# Sheet1.net
KiCad netlist of a schematic drawn in Altium Designer
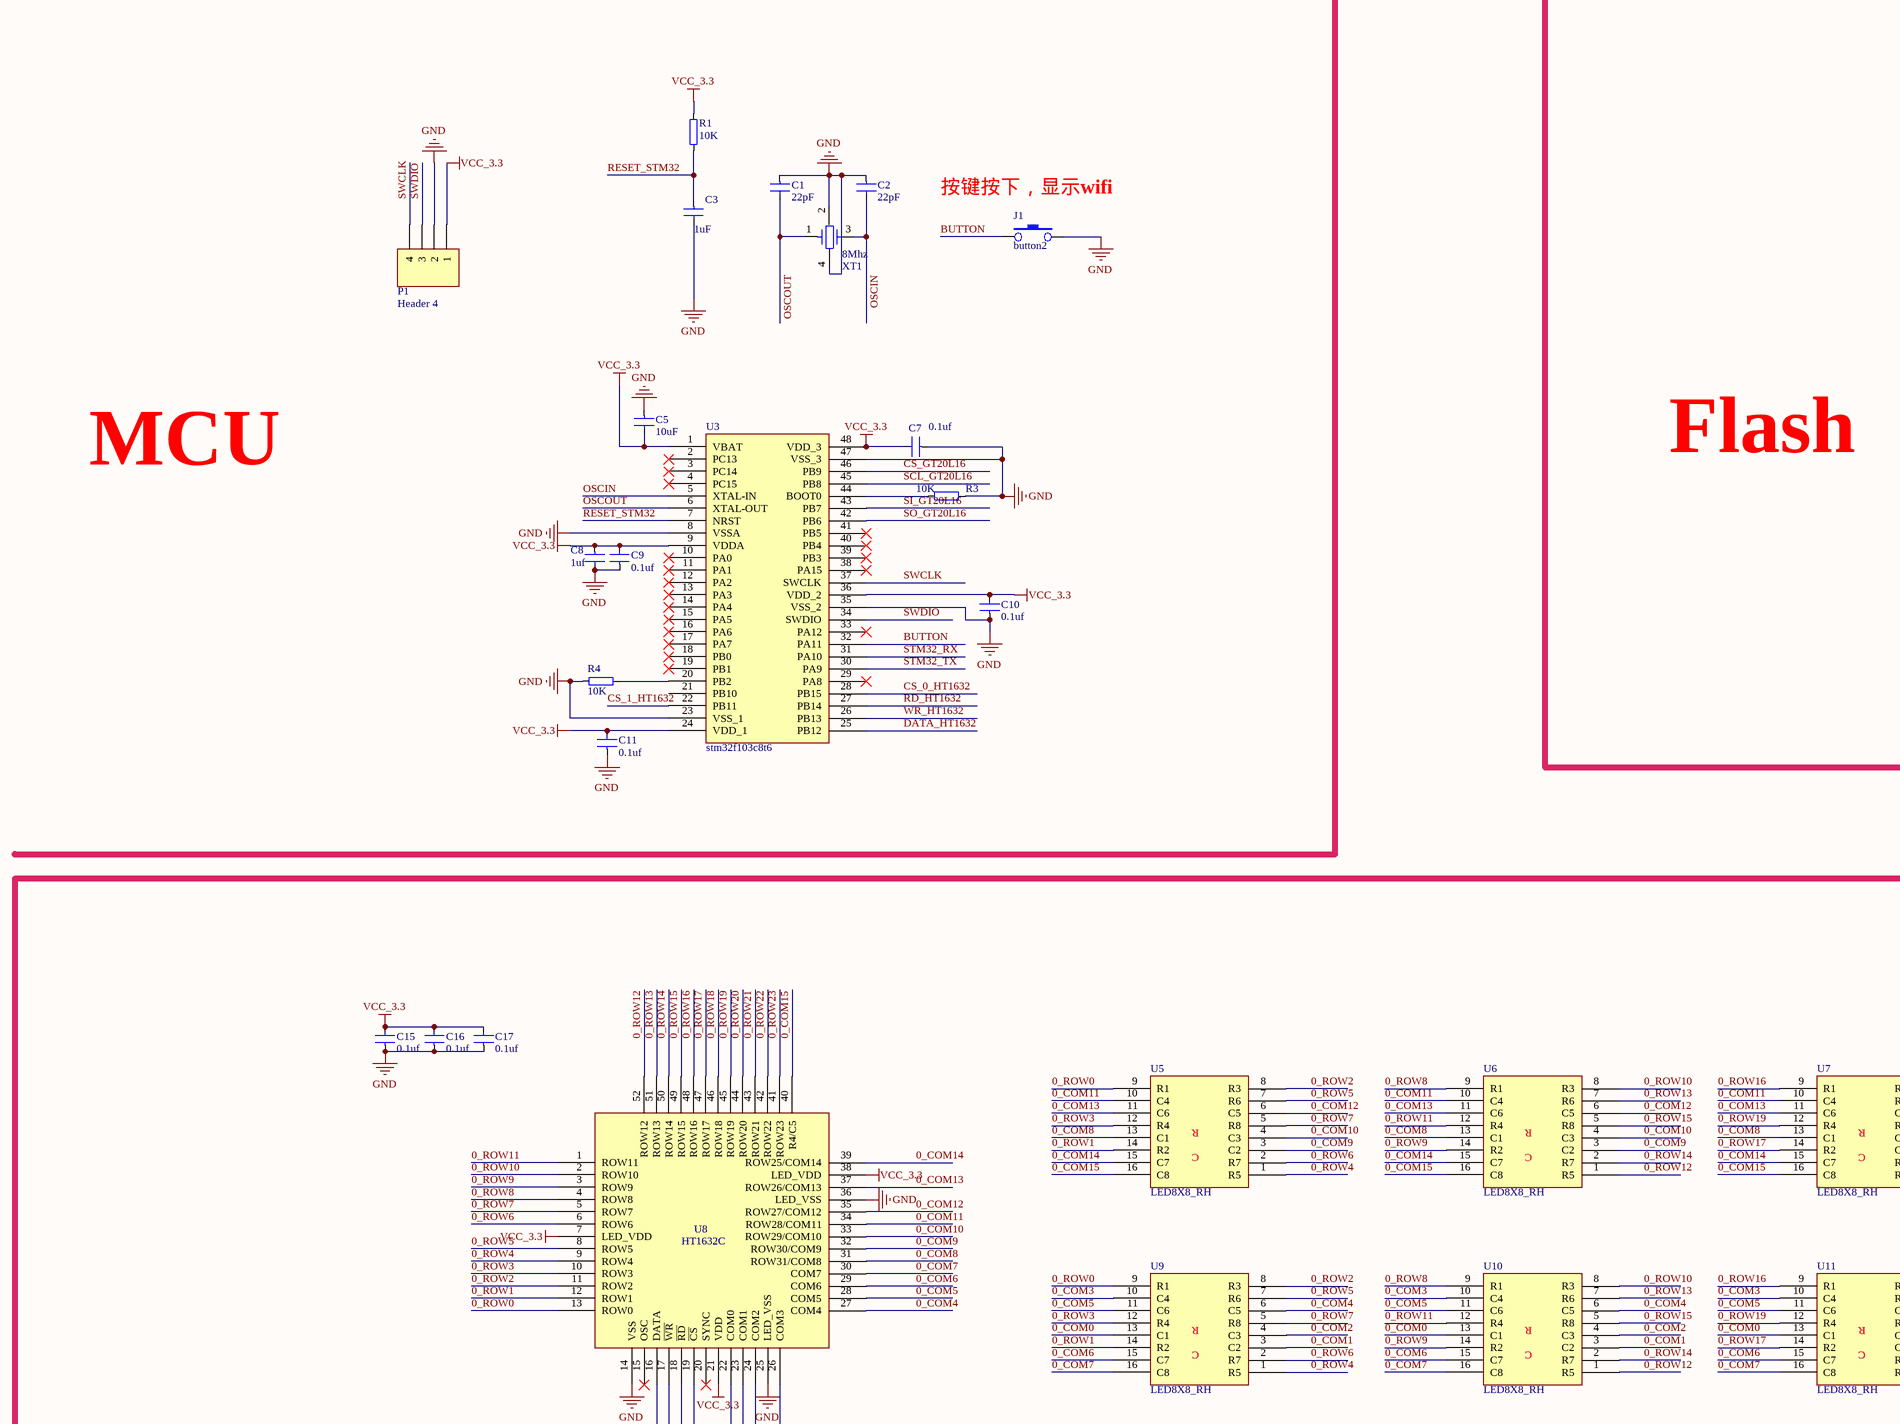
[diagram p0: Sheet1.SchDoc, top left]
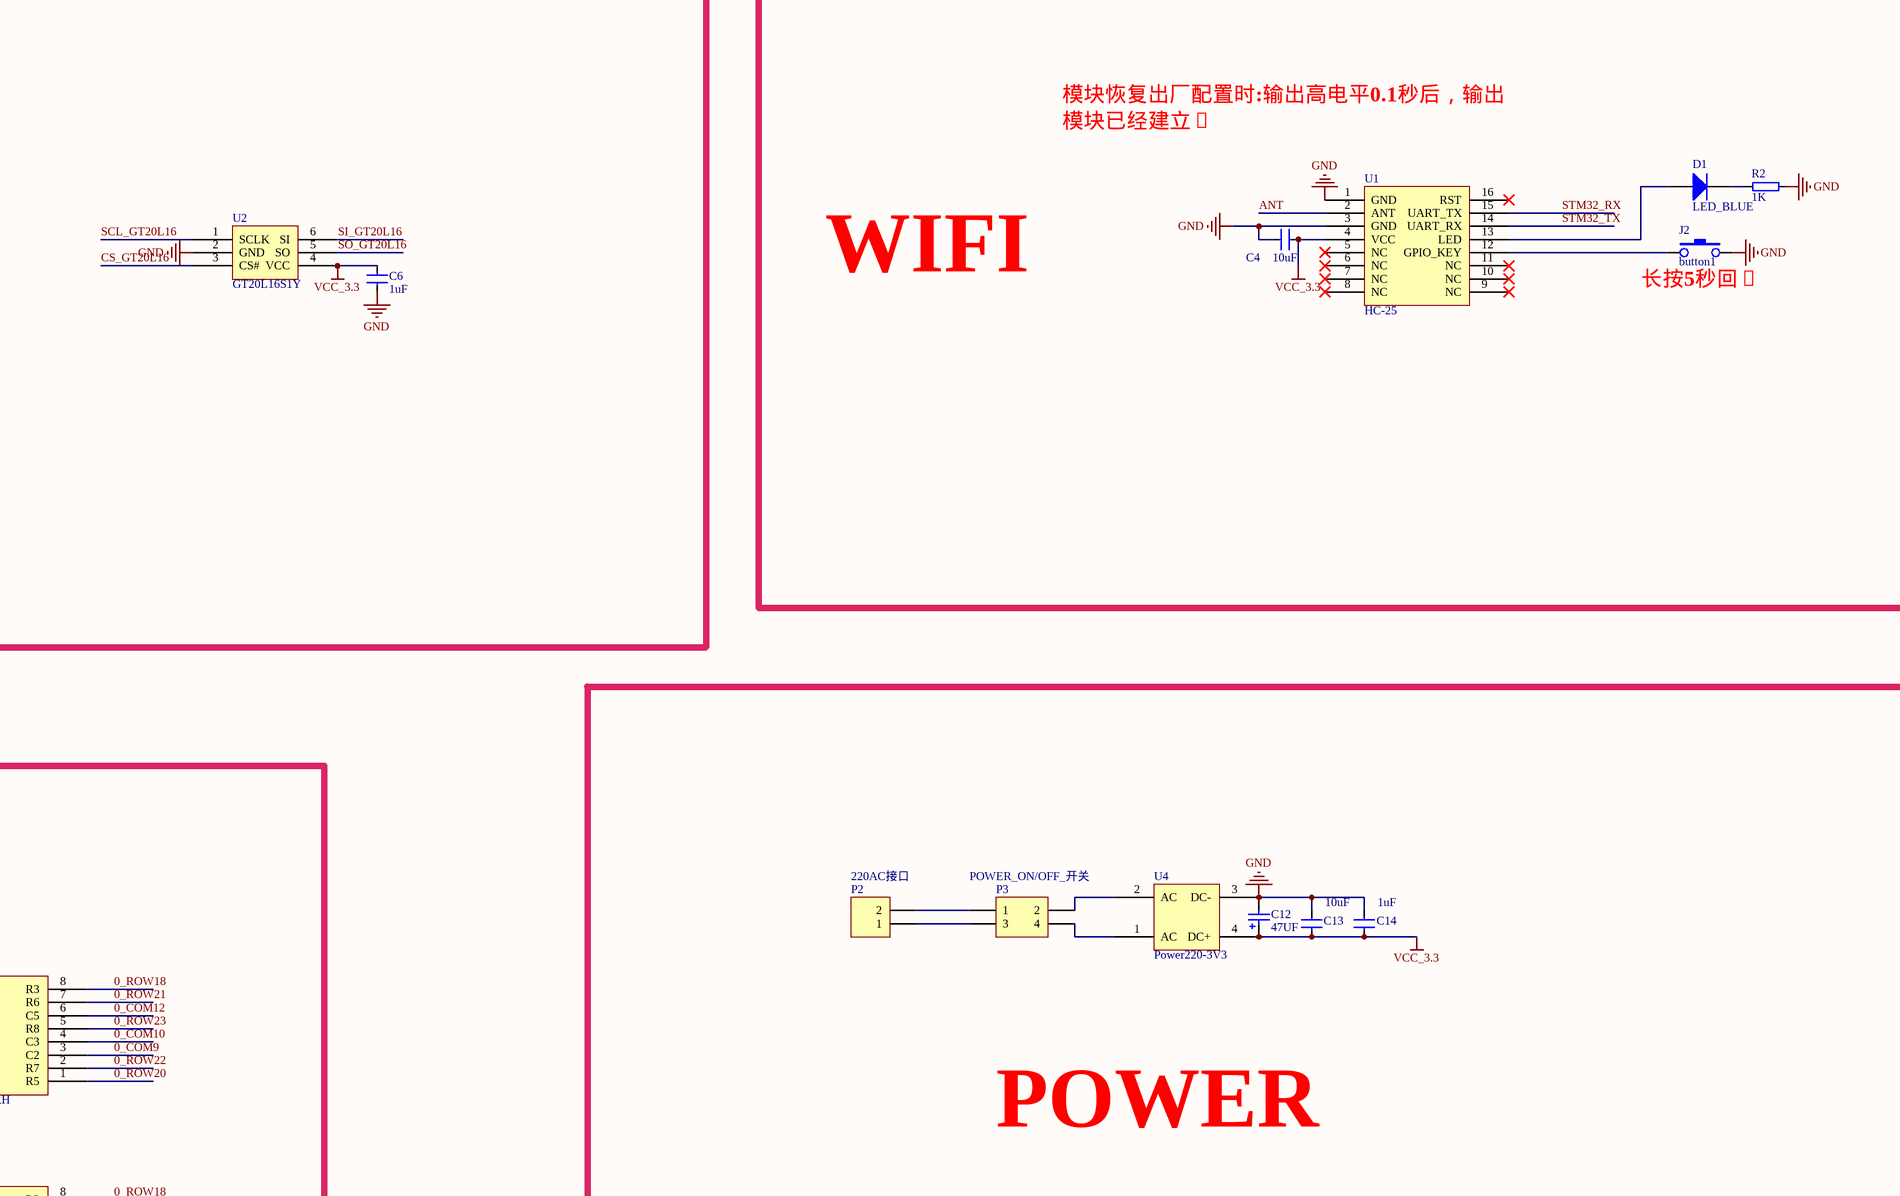
[diagram p1: Sheet1.SchDoc, top right]
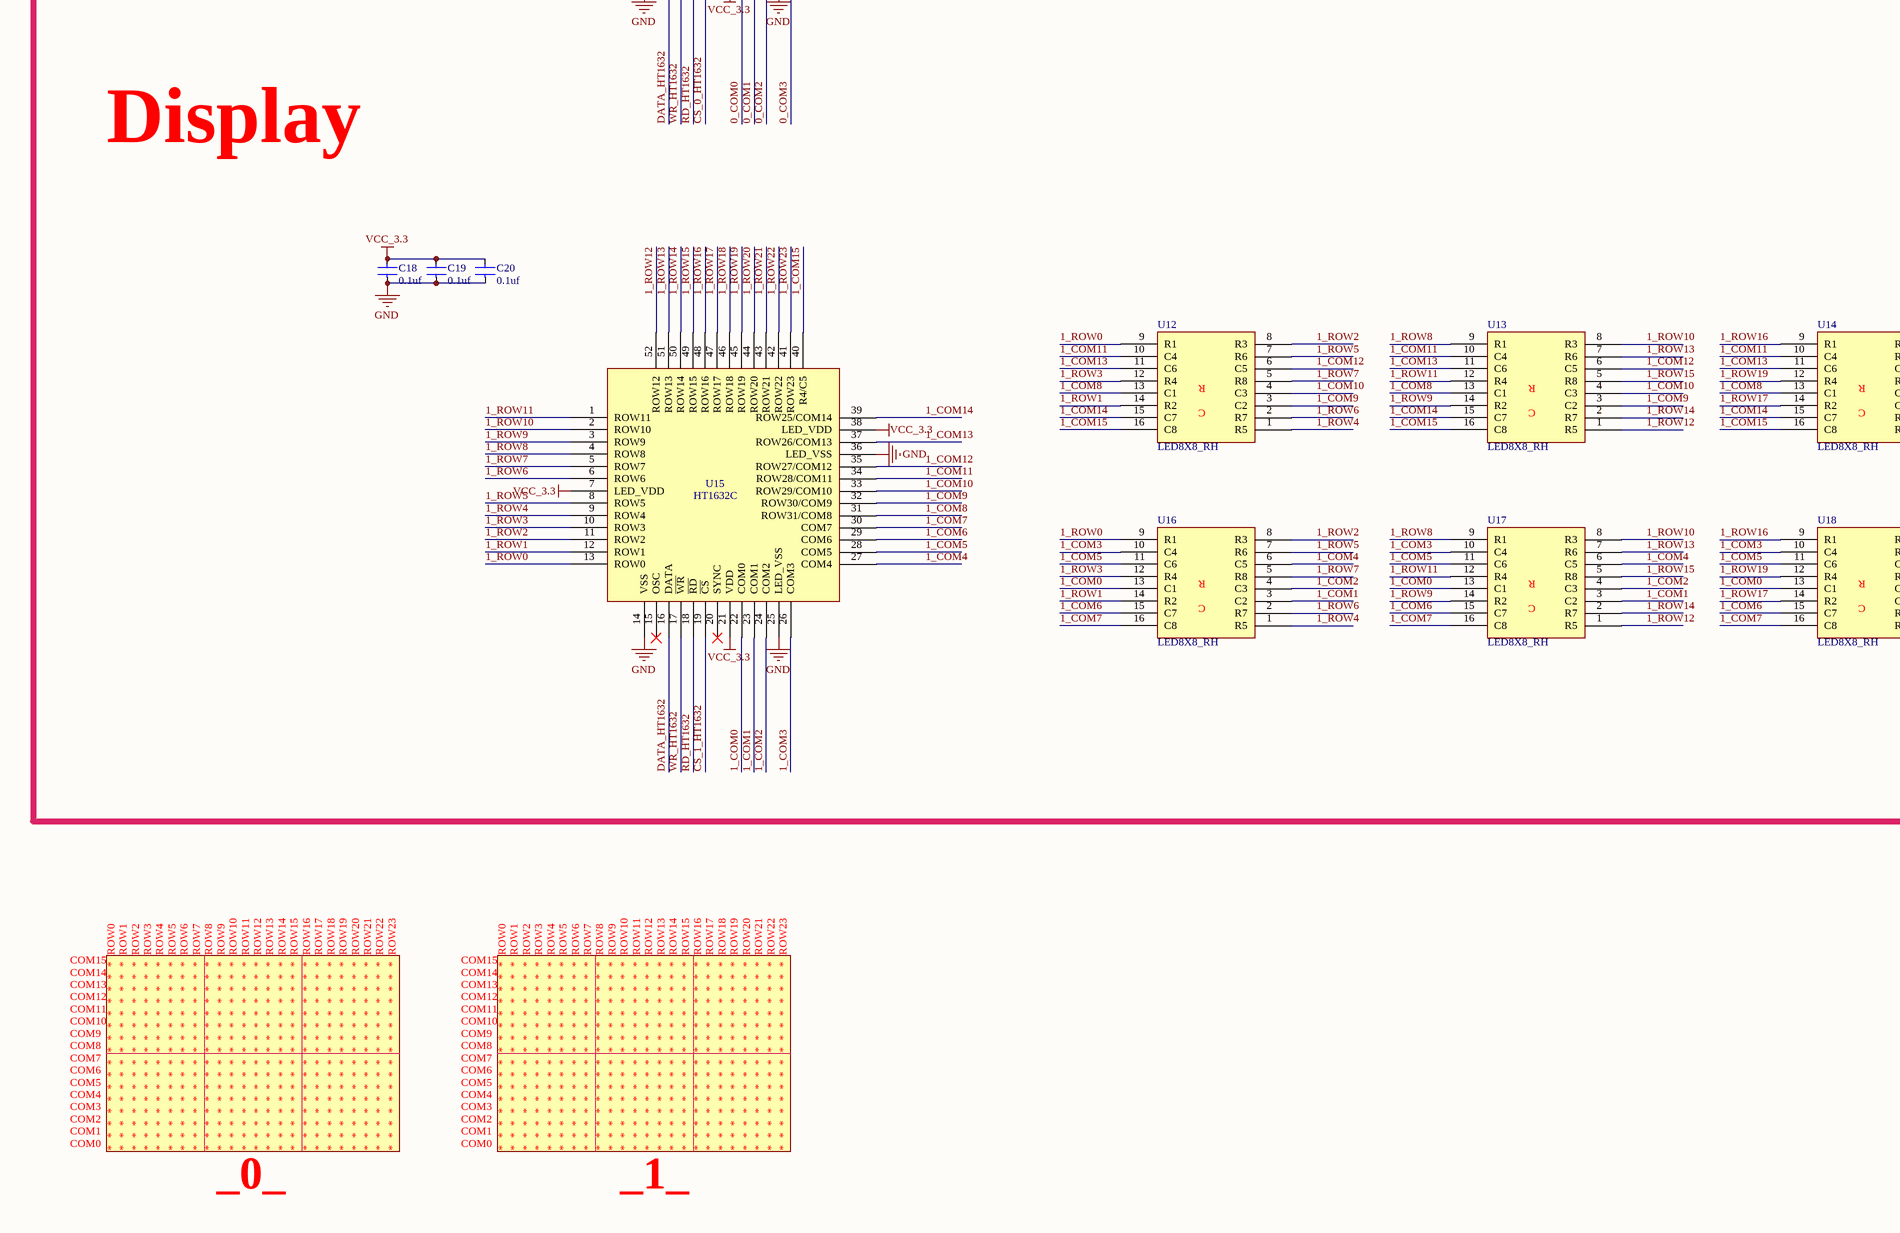
[diagram p2: Sheet1.SchDoc, bottom left]
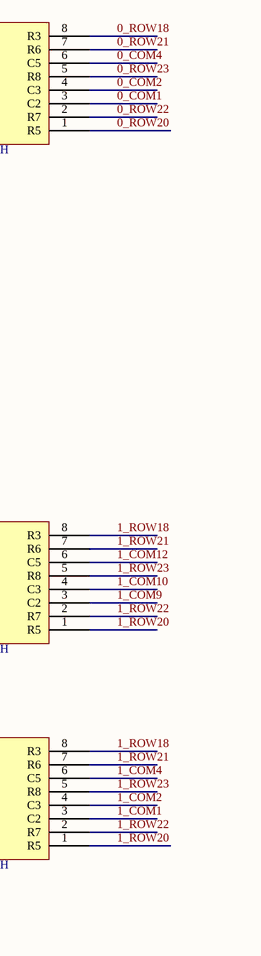
[diagram p3: Sheet1.SchDoc, bottom right]

(export (version "E")
  (design (tool "Eeschema 10.0.6"))
  (components
    (comp (ref "C1")
      (value "22pF")
      (footprint "0402-A")
      (description "SMD-CAP")
      (libsource (lib "³£ÓÃÆ÷¼þ") (part "CAP-0.1UF"))
    )
    (comp (ref "C2")
      (value "22pF")
      (footprint "0402-a")
      (description "SMD-CAP")
      (libsource (lib "³£ÓÃÆ÷¼þ") (part "CAP-0.1UF"))
    )
    (comp (ref "C3")
      (value "1uF")
      (footprint "0402-a")
      (description "SMD-CAP")
      (libsource (lib "³£ÓÃÆ÷¼þ") (part "CAP-0.1UF"))
    )
    (comp (ref "C4")
      (value "10uF")
      (footprint "0402-a")
      (description "SMD-CAP")
      (libsource (lib "³£ÓÃÆ÷¼þ") (part "CAP-0.1UF"))
    )
    (comp (ref "C5")
      (value "10uF")
      (footprint "0402-A")
      (description "SMD-CAP")
      (libsource (lib "³£ÓÃÆ÷¼þ") (part "CAP-0.1UF"))
    )
    (comp (ref "C6")
      (value "1uF")
      (footprint "0402-a")
      (description "SMD-CAP")
      (libsource (lib "³£ÓÃÆ÷¼þ") (part "CAP-0.1UF"))
    )
    (comp (ref "C7")
      (value "0.1uf")
      (footprint "0402-A")
      (description "SMD-CAP")
      (libsource (lib "³£ÓÃÆ÷¼þ") (part "CAP-0.1UF"))
    )
    (comp (ref "C8")
      (value "1uf")
      (footprint "0402-A")
      (description "SMD-CAP")
      (libsource (lib "³£ÓÃÆ÷¼þ") (part "CAP-0.1UF"))
    )
    (comp (ref "C9")
      (value "0.1uf")
      (footprint "0402-A")
      (description "SMD-CAP")
      (libsource (lib "³£ÓÃÆ÷¼þ") (part "CAP-0.1UF"))
    )
    (comp (ref "C10")
      (value "0.1uf")
      (footprint "0402-A")
      (description "SMD-CAP")
      (libsource (lib "³£ÓÃÆ÷¼þ") (part "CAP-0.1UF"))
    )
    (comp (ref "C11")
      (value "0.1uf")
      (footprint "0402-A")
      (description "SMD-CAP")
      (libsource (lib "³£ÓÃÆ÷¼þ") (part "CAP-0.1UF"))
    )
    (comp (ref "C12")
      (value "47UF")
      (footprint "POLAR0.8")
      (description "Polarized Capacitor (Axial)")
      (fields (field (name "PUBLISHER") "Altium Limited"))
      (libsource (lib "Miscellaneous Devices") (part "Cap Pol2"))
    )
    (comp (ref "C13")
      (value "10uF")
      (footprint "0402-a")
      (description "SMD-CAP")
      (libsource (lib "³£ÓÃÆ÷¼þ") (part "CAP-0.1UF"))
    )
    (comp (ref "C14")
      (value "1uF")
      (footprint "0402-a")
      (description "SMD-CAP")
      (libsource (lib "³£ÓÃÆ÷¼þ") (part "CAP-0.1UF"))
    )
    (comp (ref "C15")
      (value "0.1uf")
      (footprint "0402-A")
      (description "SMD-CAP")
      (libsource (lib "³£ÓÃÆ÷¼þ") (part "CAP-0.1UF"))
    )
    (comp (ref "C16")
      (value "0.1uf")
      (footprint "0402-A")
      (description "SMD-CAP")
      (libsource (lib "³£ÓÃÆ÷¼þ") (part "CAP-0.1UF"))
    )
    (comp (ref "C17")
      (value "0.1uf")
      (footprint "0402-A")
      (description "SMD-CAP")
      (libsource (lib "³£ÓÃÆ÷¼þ") (part "CAP-0.1UF"))
    )
    (comp (ref "C18")
      (value "0.1uf")
      (footprint "0402-A")
      (description "SMD-CAP")
      (libsource (lib "³£ÓÃÆ÷¼þ") (part "CAP-0.1UF"))
    )
    (comp (ref "C19")
      (value "0.1uf")
      (footprint "0402-A")
      (description "SMD-CAP")
      (libsource (lib "³£ÓÃÆ÷¼þ") (part "CAP-0.1UF"))
    )
    (comp (ref "C20")
      (value "0.1uf")
      (footprint "0402-A")
      (description "SMD-CAP")
      (libsource (lib "³£ÓÃÆ÷¼þ") (part "CAP-0.1UF"))
    )
    (comp (ref "D1")
      (value "LED_BLUE")
      (footprint "sod523")
      (description "Default Diode")
      (fields (field (name "PUBLISHER") "Altium Limited"))
      (libsource (lib "Miscellaneous Devices") (part "Diode"))
    )
    (comp (ref "J1") (value "button2") (footprint "BUTTON") (libsource (lib "PCB_Project1") (part "KEY")))
    (comp (ref "J2") (value "button1") (footprint "BUTTON") (libsource (lib "PCB_Project1") (part "KEY")))
    (comp (ref "P1")
      (value "Header 4")
      (footprint "HDR1X4")
      (description "Header, 4-Pin")
      (fields (field (name "PUBLISHER") "Altium Limited"))
      (libsource (lib "Miscellaneous Connectors") (part "Header 4"))
    )
    (comp (ref "P2")
      (value "220AC接口")
      (footprint "HDR1X2")
      (description "Header, 2-Pin")
      (fields (field (name "PUBLISHER") "Altium Limited"))
      (libsource (lib "Miscellaneous Connectors") (part "Header 2"))
    )
    (comp (ref "P3")
      (value "POWER_ON/OFF_开关")
      (footprint "HDR2X2")
      (description "Header, 2-Pin, Dual row")
      (fields (field (name "PUBLISHER") "Altium Limited"))
      (libsource (lib "Miscellaneous Connectors") (part "Header 2X2"))
    )
    (comp (ref "R1")
      (value "10K")
      (footprint "0402-A")
      (description "resistor")
      (libsource (lib "PCB_Project1") (part "R-10K"))
    )
    (comp (ref "R2")
      (value "1K")
      (footprint "0402-A")
      (description "resistor")
      (libsource (lib "PCB_Project1") (part "R-10K"))
    )
    (comp (ref "R3")
      (value "10K")
      (footprint "0402-A")
      (description "resistor")
      (libsource (lib "PCB_Project1") (part "R-10K"))
    )
    (comp (ref "R4")
      (value "10K")
      (footprint "0402-A")
      (description "resistor")
      (libsource (lib "PCB_Project1") (part "R-10K"))
    )
    (comp (ref "U1") (value "HC-25") (libsource (lib "Schlib1") (part "HC-25")))
    (comp (ref "U2") (value "GT20L16S1Y") (libsource (lib "Schlib1") (part "GT20L16S1Y")))
    (comp (ref "U3") (value "stm32f103c8t6") (libsource (lib "Schlib1") (part "stm32f103c8t6")))
    (comp (ref "U4") (value "Power220-3V3") (libsource (lib "Schlib1") (part "Power220-3V3")))
    (comp (ref "U5") (value "LED8X8_RH") (libsource (lib "Schlib1") (part "LED8X8_RH")))
    (comp (ref "U6") (value "LED8X8_RH") (libsource (lib "Schlib1") (part "LED8X8_RH")))
    (comp (ref "U7") (value "LED8X8_RH") (libsource (lib "Schlib1") (part "LED8X8_RH")))
    (comp (ref "U8") (value "HT1632C") (libsource (lib "Schlib1") (part "HT1632C")))
    (comp (ref "U9") (value "LED8X8_RH") (libsource (lib "Schlib1") (part "LED8X8_RH")))
    (comp (ref "U10") (value "LED8X8_RH") (libsource (lib "Schlib1") (part "LED8X8_RH")))
    (comp (ref "U11") (value "LED8X8_RH") (libsource (lib "Schlib1") (part "LED8X8_RH")))
    (comp (ref "U12") (value "LED8X8_RH") (libsource (lib "Schlib1") (part "LED8X8_RH")))
    (comp (ref "U13") (value "LED8X8_RH") (libsource (lib "Schlib1") (part "LED8X8_RH")))
    (comp (ref "U14") (value "LED8X8_RH") (libsource (lib "Schlib1") (part "LED8X8_RH")))
    (comp (ref "U15") (value "HT1632C") (libsource (lib "Schlib1") (part "HT1632C")))
    (comp (ref "U16") (value "LED8X8_RH") (libsource (lib "Schlib1") (part "LED8X8_RH")))
    (comp (ref "U17") (value "LED8X8_RH") (libsource (lib "Schlib1") (part "LED8X8_RH")))
    (comp (ref "U18") (value "LED8X8_RH") (libsource (lib "Schlib1") (part "LED8X8_RH")))
    (comp (ref "XT1")
      (value "8Mhz")
      (footprint "SMD3225")
      (description "晶振")
      (libsource (lib "PCB_Project1") (part "XT"))
    )
  )
  (nets
    (net (code "1") (name "/0_COM0") (class "Default")
      (node (ref "U10") (pin "13") (pinfunction "C1_13") (pintype "passive"))
      (node (ref "U11") (pin "13") (pinfunction "C1_13") (pintype "passive"))
      (node (ref "U8") (pin "22") (pinfunction "COM0_22") (pintype "passive"))
      (node (ref "U9") (pin "13") (pinfunction "C1_13") (pintype "passive"))
    )
    (net (code "2") (name "/0_COM1") (class "Default")
      (node (ref "U10") (pin "3") (pinfunction "C2_3") (pintype "passive"))
      (node (ref "U11") (pin "3") (pinfunction "C2_3") (pintype "passive"))
      (node (ref "U8") (pin "23") (pinfunction "COM1_23") (pintype "passive"))
      (node (ref "U9") (pin "3") (pinfunction "C2_3") (pintype "passive"))
    )
    (net (code "3") (name "/0_COM2") (class "Default")
      (node (ref "U10") (pin "4") (pinfunction "C3_4") (pintype "passive"))
      (node (ref "U11") (pin "4") (pinfunction "C3_4") (pintype "passive"))
      (node (ref "U8") (pin "24") (pinfunction "COM2_24") (pintype "passive"))
      (node (ref "U9") (pin "4") (pinfunction "C3_4") (pintype "passive"))
    )
    (net (code "4") (name "/0_COM3") (class "Default")
      (node (ref "U10") (pin "10") (pinfunction "C4_10") (pintype "passive"))
      (node (ref "U11") (pin "10") (pinfunction "C4_10") (pintype "passive"))
      (node (ref "U8") (pin "26") (pinfunction "COM3_26") (pintype "passive"))
      (node (ref "U9") (pin "10") (pinfunction "C4_10") (pintype "passive"))
    )
    (net (code "5") (name "/0_COM4") (class "Default")
      (node (ref "U10") (pin "6") (pinfunction "C5_6") (pintype "passive"))
      (node (ref "U11") (pin "6") (pinfunction "C5_6") (pintype "passive"))
      (node (ref "U8") (pin "27") (pinfunction "COM4_27") (pintype "passive"))
      (node (ref "U9") (pin "6") (pinfunction "C5_6") (pintype "passive"))
    )
    (net (code "6") (name "/0_COM5") (class "Default")
      (node (ref "U10") (pin "11") (pinfunction "C6_11") (pintype "passive"))
      (node (ref "U11") (pin "11") (pinfunction "C6_11") (pintype "passive"))
      (node (ref "U8") (pin "28") (pinfunction "COM5_28") (pintype "passive"))
      (node (ref "U9") (pin "11") (pinfunction "C6_11") (pintype "passive"))
    )
    (net (code "7") (name "/0_COM6") (class "Default")
      (node (ref "U10") (pin "15") (pinfunction "C7_15") (pintype "passive"))
      (node (ref "U11") (pin "15") (pinfunction "C7_15") (pintype "passive"))
      (node (ref "U8") (pin "29") (pinfunction "COM6_29") (pintype "passive"))
      (node (ref "U9") (pin "15") (pinfunction "C7_15") (pintype "passive"))
    )
    (net (code "8") (name "/0_COM7") (class "Default")
      (node (ref "U10") (pin "16") (pinfunction "C8_16") (pintype "passive"))
      (node (ref "U11") (pin "16") (pinfunction "C8_16") (pintype "passive"))
      (node (ref "U8") (pin "30") (pinfunction "COM7_30") (pintype "passive"))
      (node (ref "U9") (pin "16") (pinfunction "C8_16") (pintype "passive"))
    )
    (net (code "9") (name "/0_COM8") (class "Default")
      (node (ref "U5") (pin "13") (pinfunction "C1_13") (pintype "passive"))
      (node (ref "U6") (pin "13") (pinfunction "C1_13") (pintype "passive"))
      (node (ref "U7") (pin "13") (pinfunction "C1_13") (pintype "passive"))
      (node (ref "U8") (pin "31") (pinfunction "ROW31/COM8_31") (pintype "passive"))
    )
    (net (code "10") (name "/0_COM9") (class "Default")
      (node (ref "U5") (pin "3") (pinfunction "C2_3") (pintype "passive"))
      (node (ref "U6") (pin "3") (pinfunction "C2_3") (pintype "passive"))
      (node (ref "U7") (pin "3") (pinfunction "C2_3") (pintype "passive"))
      (node (ref "U8") (pin "32") (pinfunction "ROW30/COM9_32") (pintype "passive"))
    )
    (net (code "11") (name "/0_COM10") (class "Default")
      (node (ref "U5") (pin "4") (pinfunction "C3_4") (pintype "passive"))
      (node (ref "U6") (pin "4") (pinfunction "C3_4") (pintype "passive"))
      (node (ref "U7") (pin "4") (pinfunction "C3_4") (pintype "passive"))
      (node (ref "U8") (pin "33") (pinfunction "ROW29/COM10_33") (pintype "passive"))
    )
    (net (code "12") (name "/0_COM11") (class "Default")
      (node (ref "U5") (pin "10") (pinfunction "C4_10") (pintype "passive"))
      (node (ref "U6") (pin "10") (pinfunction "C4_10") (pintype "passive"))
      (node (ref "U7") (pin "10") (pinfunction "C4_10") (pintype "passive"))
      (node (ref "U8") (pin "34") (pinfunction "ROW28/COM11_34") (pintype "passive"))
    )
    (net (code "13") (name "/0_COM12") (class "Default")
      (node (ref "U5") (pin "6") (pinfunction "C5_6") (pintype "passive"))
      (node (ref "U6") (pin "6") (pinfunction "C5_6") (pintype "passive"))
      (node (ref "U7") (pin "6") (pinfunction "C5_6") (pintype "passive"))
      (node (ref "U8") (pin "35") (pinfunction "ROW27/COM12_35") (pintype "passive"))
    )
    (net (code "14") (name "/0_COM13") (class "Default")
      (node (ref "U5") (pin "11") (pinfunction "C6_11") (pintype "passive"))
      (node (ref "U6") (pin "11") (pinfunction "C6_11") (pintype "passive"))
      (node (ref "U7") (pin "11") (pinfunction "C6_11") (pintype "passive"))
      (node (ref "U8") (pin "37") (pinfunction "ROW26/COM13_37") (pintype "passive"))
    )
    (net (code "15") (name "/0_COM14") (class "Default")
      (node (ref "U5") (pin "15") (pinfunction "C7_15") (pintype "passive"))
      (node (ref "U6") (pin "15") (pinfunction "C7_15") (pintype "passive"))
      (node (ref "U7") (pin "15") (pinfunction "C7_15") (pintype "passive"))
      (node (ref "U8") (pin "39") (pinfunction "ROW25/COM14_39") (pintype "passive"))
    )
    (net (code "16") (name "/0_COM15") (class "Default")
      (node (ref "U5") (pin "16") (pinfunction "C8_16") (pintype "passive"))
      (node (ref "U6") (pin "16") (pinfunction "C8_16") (pintype "passive"))
      (node (ref "U7") (pin "16") (pinfunction "C8_16") (pintype "passive"))
      (node (ref "U8") (pin "40") (pinfunction "R4/C5_40") (pintype "passive"))
    )
    (net (code "17") (name "/0_ROW0") (class "Default")
      (node (ref "U5") (pin "9") (pinfunction "R1_9") (pintype "passive"))
      (node (ref "U8") (pin "13") (pinfunction "ROW0_13") (pintype "passive"))
      (node (ref "U9") (pin "9") (pinfunction "R1_9") (pintype "passive"))
    )
    (net (code "18") (name "/0_ROW1") (class "Default")
      (node (ref "U5") (pin "14") (pinfunction "R2_14") (pintype "passive"))
      (node (ref "U8") (pin "12") (pinfunction "ROW1_12") (pintype "passive"))
      (node (ref "U9") (pin "14") (pinfunction "R2_14") (pintype "passive"))
    )
    (net (code "19") (name "/0_ROW2") (class "Default")
      (node (ref "U5") (pin "8") (pinfunction "R3_8") (pintype "passive"))
      (node (ref "U8") (pin "11") (pinfunction "ROW2_11") (pintype "passive"))
      (node (ref "U9") (pin "8") (pinfunction "R3_8") (pintype "passive"))
    )
    (net (code "20") (name "/0_ROW3") (class "Default")
      (node (ref "U5") (pin "12") (pinfunction "R4_12") (pintype "passive"))
      (node (ref "U8") (pin "10") (pinfunction "ROW3_10") (pintype "passive"))
      (node (ref "U9") (pin "12") (pinfunction "R4_12") (pintype "passive"))
    )
    (net (code "21") (name "/0_ROW4") (class "Default")
      (node (ref "U5") (pin "1") (pinfunction "R5_1") (pintype "passive"))
      (node (ref "U8") (pin "9") (pinfunction "ROW4_9") (pintype "passive"))
      (node (ref "U9") (pin "1") (pinfunction "R5_1") (pintype "passive"))
    )
    (net (code "22") (name "/0_ROW5") (class "Default")
      (node (ref "U5") (pin "7") (pinfunction "R6_7") (pintype "passive"))
      (node (ref "U8") (pin "8") (pinfunction "ROW5_8") (pintype "passive"))
      (node (ref "U9") (pin "7") (pinfunction "R6_7") (pintype "passive"))
    )
    (net (code "23") (name "/0_ROW6") (class "Default")
      (node (ref "U5") (pin "2") (pinfunction "R7_2") (pintype "passive"))
      (node (ref "U8") (pin "6") (pinfunction "ROW6_6") (pintype "passive"))
      (node (ref "U9") (pin "2") (pinfunction "R7_2") (pintype "passive"))
    )
    (net (code "24") (name "/0_ROW7") (class "Default")
      (node (ref "U5") (pin "5") (pinfunction "R8_5") (pintype "passive"))
      (node (ref "U8") (pin "5") (pinfunction "ROW7_5") (pintype "passive"))
      (node (ref "U9") (pin "5") (pinfunction "R8_5") (pintype "passive"))
    )
    (net (code "25") (name "/0_ROW8") (class "Default")
      (node (ref "U10") (pin "9") (pinfunction "R1_9") (pintype "passive"))
      (node (ref "U6") (pin "9") (pinfunction "R1_9") (pintype "passive"))
      (node (ref "U8") (pin "4") (pinfunction "ROW8_4") (pintype "passive"))
    )
    (net (code "26") (name "/0_ROW9") (class "Default")
      (node (ref "U10") (pin "14") (pinfunction "R2_14") (pintype "passive"))
      (node (ref "U6") (pin "14") (pinfunction "R2_14") (pintype "passive"))
      (node (ref "U8") (pin "3") (pinfunction "ROW9_3") (pintype "passive"))
    )
    (net (code "27") (name "/0_ROW10") (class "Default")
      (node (ref "U10") (pin "8") (pinfunction "R3_8") (pintype "passive"))
      (node (ref "U6") (pin "8") (pinfunction "R3_8") (pintype "passive"))
      (node (ref "U8") (pin "2") (pinfunction "ROW10_2") (pintype "passive"))
    )
    (net (code "28") (name "/0_ROW11") (class "Default")
      (node (ref "U10") (pin "12") (pinfunction "R4_12") (pintype "passive"))
      (node (ref "U6") (pin "12") (pinfunction "R4_12") (pintype "passive"))
      (node (ref "U8") (pin "1") (pinfunction "ROW11_1") (pintype "passive"))
    )
    (net (code "29") (name "/0_ROW12") (class "Default")
      (node (ref "U10") (pin "1") (pinfunction "R5_1") (pintype "passive"))
      (node (ref "U6") (pin "1") (pinfunction "R5_1") (pintype "passive"))
      (node (ref "U8") (pin "52") (pinfunction "ROW12_52") (pintype "passive"))
    )
    (net (code "30") (name "/0_ROW13") (class "Default")
      (node (ref "U10") (pin "7") (pinfunction "R6_7") (pintype "passive"))
      (node (ref "U6") (pin "7") (pinfunction "R6_7") (pintype "passive"))
      (node (ref "U8") (pin "51") (pinfunction "ROW13_51") (pintype "passive"))
    )
    (net (code "31") (name "/0_ROW14") (class "Default")
      (node (ref "U10") (pin "2") (pinfunction "R7_2") (pintype "passive"))
      (node (ref "U6") (pin "2") (pinfunction "R7_2") (pintype "passive"))
      (node (ref "U8") (pin "50") (pinfunction "ROW14_50") (pintype "passive"))
    )
    (net (code "32") (name "/0_ROW15") (class "Default")
      (node (ref "U10") (pin "5") (pinfunction "R8_5") (pintype "passive"))
      (node (ref "U6") (pin "5") (pinfunction "R8_5") (pintype "passive"))
      (node (ref "U8") (pin "49") (pinfunction "ROW15_49") (pintype "passive"))
    )
    (net (code "33") (name "/0_ROW16") (class "Default")
      (node (ref "U11") (pin "9") (pinfunction "R1_9") (pintype "passive"))
      (node (ref "U7") (pin "9") (pinfunction "R1_9") (pintype "passive"))
      (node (ref "U8") (pin "48") (pinfunction "ROW16_48") (pintype "passive"))
    )
    (net (code "34") (name "/0_ROW17") (class "Default")
      (node (ref "U11") (pin "14") (pinfunction "R2_14") (pintype "passive"))
      (node (ref "U7") (pin "14") (pinfunction "R2_14") (pintype "passive"))
      (node (ref "U8") (pin "47") (pinfunction "ROW17_47") (pintype "passive"))
    )
    (net (code "35") (name "/0_ROW18") (class "Default")
      (node (ref "U11") (pin "8") (pinfunction "R3_8") (pintype "passive"))
      (node (ref "U7") (pin "8") (pinfunction "R3_8") (pintype "passive"))
      (node (ref "U8") (pin "46") (pinfunction "ROW18_46") (pintype "passive"))
    )
    (net (code "36") (name "/0_ROW19") (class "Default")
      (node (ref "U11") (pin "12") (pinfunction "R4_12") (pintype "passive"))
      (node (ref "U7") (pin "12") (pinfunction "R4_12") (pintype "passive"))
      (node (ref "U8") (pin "45") (pinfunction "ROW19_45") (pintype "passive"))
    )
    (net (code "37") (name "/0_ROW20") (class "Default")
      (node (ref "U11") (pin "1") (pinfunction "R5_1") (pintype "passive"))
      (node (ref "U7") (pin "1") (pinfunction "R5_1") (pintype "passive"))
      (node (ref "U8") (pin "44") (pinfunction "ROW20_44") (pintype "passive"))
    )
    (net (code "38") (name "/0_ROW21") (class "Default")
      (node (ref "U11") (pin "7") (pinfunction "R6_7") (pintype "passive"))
      (node (ref "U7") (pin "7") (pinfunction "R6_7") (pintype "passive"))
      (node (ref "U8") (pin "43") (pinfunction "ROW21_43") (pintype "passive"))
    )
    (net (code "39") (name "/0_ROW22") (class "Default")
      (node (ref "U11") (pin "2") (pinfunction "R7_2") (pintype "passive"))
      (node (ref "U7") (pin "2") (pinfunction "R7_2") (pintype "passive"))
      (node (ref "U8") (pin "42") (pinfunction "ROW22_42") (pintype "passive"))
    )
    (net (code "40") (name "/0_ROW23") (class "Default")
      (node (ref "U11") (pin "5") (pinfunction "R8_5") (pintype "passive"))
      (node (ref "U7") (pin "5") (pinfunction "R8_5") (pintype "passive"))
      (node (ref "U8") (pin "41") (pinfunction "ROW23_41") (pintype "passive"))
    )
    (net (code "41") (name "/1_COM0") (class "Default")
      (node (ref "U15") (pin "22") (pinfunction "COM0_22") (pintype "passive"))
      (node (ref "U16") (pin "13") (pinfunction "C1_13") (pintype "passive"))
      (node (ref "U17") (pin "13") (pinfunction "C1_13") (pintype "passive"))
      (node (ref "U18") (pin "13") (pinfunction "C1_13") (pintype "passive"))
    )
    (net (code "42") (name "/1_COM1") (class "Default")
      (node (ref "U15") (pin "23") (pinfunction "COM1_23") (pintype "passive"))
      (node (ref "U16") (pin "3") (pinfunction "C2_3") (pintype "passive"))
      (node (ref "U17") (pin "3") (pinfunction "C2_3") (pintype "passive"))
      (node (ref "U18") (pin "3") (pinfunction "C2_3") (pintype "passive"))
    )
    (net (code "43") (name "/1_COM2") (class "Default")
      (node (ref "U15") (pin "24") (pinfunction "COM2_24") (pintype "passive"))
      (node (ref "U16") (pin "4") (pinfunction "C3_4") (pintype "passive"))
      (node (ref "U17") (pin "4") (pinfunction "C3_4") (pintype "passive"))
      (node (ref "U18") (pin "4") (pinfunction "C3_4") (pintype "passive"))
    )
    (net (code "44") (name "/1_COM3") (class "Default")
      (node (ref "U15") (pin "26") (pinfunction "COM3_26") (pintype "passive"))
      (node (ref "U16") (pin "10") (pinfunction "C4_10") (pintype "passive"))
      (node (ref "U17") (pin "10") (pinfunction "C4_10") (pintype "passive"))
      (node (ref "U18") (pin "10") (pinfunction "C4_10") (pintype "passive"))
    )
    (net (code "45") (name "/1_COM4") (class "Default")
      (node (ref "U15") (pin "27") (pinfunction "COM4_27") (pintype "passive"))
      (node (ref "U16") (pin "6") (pinfunction "C5_6") (pintype "passive"))
      (node (ref "U17") (pin "6") (pinfunction "C5_6") (pintype "passive"))
      (node (ref "U18") (pin "6") (pinfunction "C5_6") (pintype "passive"))
    )
    (net (code "46") (name "/1_COM5") (class "Default")
      (node (ref "U15") (pin "28") (pinfunction "COM5_28") (pintype "passive"))
      (node (ref "U16") (pin "11") (pinfunction "C6_11") (pintype "passive"))
      (node (ref "U17") (pin "11") (pinfunction "C6_11") (pintype "passive"))
      (node (ref "U18") (pin "11") (pinfunction "C6_11") (pintype "passive"))
    )
    (net (code "47") (name "/1_COM6") (class "Default")
      (node (ref "U15") (pin "29") (pinfunction "COM6_29") (pintype "passive"))
      (node (ref "U16") (pin "15") (pinfunction "C7_15") (pintype "passive"))
      (node (ref "U17") (pin "15") (pinfunction "C7_15") (pintype "passive"))
      (node (ref "U18") (pin "15") (pinfunction "C7_15") (pintype "passive"))
    )
    (net (code "48") (name "/1_COM7") (class "Default")
      (node (ref "U15") (pin "30") (pinfunction "COM7_30") (pintype "passive"))
      (node (ref "U16") (pin "16") (pinfunction "C8_16") (pintype "passive"))
      (node (ref "U17") (pin "16") (pinfunction "C8_16") (pintype "passive"))
      (node (ref "U18") (pin "16") (pinfunction "C8_16") (pintype "passive"))
    )
    (net (code "49") (name "/1_COM8") (class "Default")
      (node (ref "U12") (pin "13") (pinfunction "C1_13") (pintype "passive"))
      (node (ref "U13") (pin "13") (pinfunction "C1_13") (pintype "passive"))
      (node (ref "U14") (pin "13") (pinfunction "C1_13") (pintype "passive"))
      (node (ref "U15") (pin "31") (pinfunction "ROW31/COM8_31") (pintype "passive"))
    )
    (net (code "50") (name "/1_COM9") (class "Default")
      (node (ref "U12") (pin "3") (pinfunction "C2_3") (pintype "passive"))
      (node (ref "U13") (pin "3") (pinfunction "C2_3") (pintype "passive"))
      (node (ref "U14") (pin "3") (pinfunction "C2_3") (pintype "passive"))
      (node (ref "U15") (pin "32") (pinfunction "ROW30/COM9_32") (pintype "passive"))
    )
    (net (code "51") (name "/1_COM10") (class "Default")
      (node (ref "U12") (pin "4") (pinfunction "C3_4") (pintype "passive"))
      (node (ref "U13") (pin "4") (pinfunction "C3_4") (pintype "passive"))
      (node (ref "U14") (pin "4") (pinfunction "C3_4") (pintype "passive"))
      (node (ref "U15") (pin "33") (pinfunction "ROW29/COM10_33") (pintype "passive"))
    )
    (net (code "52") (name "/1_COM11") (class "Default")
      (node (ref "U12") (pin "10") (pinfunction "C4_10") (pintype "passive"))
      (node (ref "U13") (pin "10") (pinfunction "C4_10") (pintype "passive"))
      (node (ref "U14") (pin "10") (pinfunction "C4_10") (pintype "passive"))
      (node (ref "U15") (pin "34") (pinfunction "ROW28/COM11_34") (pintype "passive"))
    )
    (net (code "53") (name "/1_COM12") (class "Default")
      (node (ref "U12") (pin "6") (pinfunction "C5_6") (pintype "passive"))
      (node (ref "U13") (pin "6") (pinfunction "C5_6") (pintype "passive"))
      (node (ref "U14") (pin "6") (pinfunction "C5_6") (pintype "passive"))
      (node (ref "U15") (pin "35") (pinfunction "ROW27/COM12_35") (pintype "passive"))
    )
    (net (code "54") (name "/1_COM13") (class "Default")
      (node (ref "U12") (pin "11") (pinfunction "C6_11") (pintype "passive"))
      (node (ref "U13") (pin "11") (pinfunction "C6_11") (pintype "passive"))
      (node (ref "U14") (pin "11") (pinfunction "C6_11") (pintype "passive"))
      (node (ref "U15") (pin "37") (pinfunction "ROW26/COM13_37") (pintype "passive"))
    )
    (net (code "55") (name "/1_COM14") (class "Default")
      (node (ref "U12") (pin "15") (pinfunction "C7_15") (pintype "passive"))
      (node (ref "U13") (pin "15") (pinfunction "C7_15") (pintype "passive"))
      (node (ref "U14") (pin "15") (pinfunction "C7_15") (pintype "passive"))
      (node (ref "U15") (pin "39") (pinfunction "ROW25/COM14_39") (pintype "passive"))
    )
    (net (code "56") (name "/1_COM15") (class "Default")
      (node (ref "U12") (pin "16") (pinfunction "C8_16") (pintype "passive"))
      (node (ref "U13") (pin "16") (pinfunction "C8_16") (pintype "passive"))
      (node (ref "U14") (pin "16") (pinfunction "C8_16") (pintype "passive"))
      (node (ref "U15") (pin "40") (pinfunction "R4/C5_40") (pintype "passive"))
    )
    (net (code "57") (name "/1_ROW0") (class "Default")
      (node (ref "U12") (pin "9") (pinfunction "R1_9") (pintype "passive"))
      (node (ref "U15") (pin "13") (pinfunction "ROW0_13") (pintype "passive"))
      (node (ref "U16") (pin "9") (pinfunction "R1_9") (pintype "passive"))
    )
    (net (code "58") (name "/1_ROW1") (class "Default")
      (node (ref "U12") (pin "14") (pinfunction "R2_14") (pintype "passive"))
      (node (ref "U15") (pin "12") (pinfunction "ROW1_12") (pintype "passive"))
      (node (ref "U16") (pin "14") (pinfunction "R2_14") (pintype "passive"))
    )
    (net (code "59") (name "/1_ROW2") (class "Default")
      (node (ref "U12") (pin "8") (pinfunction "R3_8") (pintype "passive"))
      (node (ref "U15") (pin "11") (pinfunction "ROW2_11") (pintype "passive"))
      (node (ref "U16") (pin "8") (pinfunction "R3_8") (pintype "passive"))
    )
    (net (code "60") (name "/1_ROW3") (class "Default")
      (node (ref "U12") (pin "12") (pinfunction "R4_12") (pintype "passive"))
      (node (ref "U15") (pin "10") (pinfunction "ROW3_10") (pintype "passive"))
      (node (ref "U16") (pin "12") (pinfunction "R4_12") (pintype "passive"))
    )
    (net (code "61") (name "/1_ROW4") (class "Default")
      (node (ref "U12") (pin "1") (pinfunction "R5_1") (pintype "passive"))
      (node (ref "U15") (pin "9") (pinfunction "ROW4_9") (pintype "passive"))
      (node (ref "U16") (pin "1") (pinfunction "R5_1") (pintype "passive"))
    )
    (net (code "62") (name "/1_ROW5") (class "Default")
      (node (ref "U12") (pin "7") (pinfunction "R6_7") (pintype "passive"))
      (node (ref "U15") (pin "8") (pinfunction "ROW5_8") (pintype "passive"))
      (node (ref "U16") (pin "7") (pinfunction "R6_7") (pintype "passive"))
    )
    (net (code "63") (name "/1_ROW6") (class "Default")
      (node (ref "U12") (pin "2") (pinfunction "R7_2") (pintype "passive"))
      (node (ref "U15") (pin "6") (pinfunction "ROW6_6") (pintype "passive"))
      (node (ref "U16") (pin "2") (pinfunction "R7_2") (pintype "passive"))
    )
    (net (code "64") (name "/1_ROW7") (class "Default")
      (node (ref "U12") (pin "5") (pinfunction "R8_5") (pintype "passive"))
      (node (ref "U15") (pin "5") (pinfunction "ROW7_5") (pintype "passive"))
      (node (ref "U16") (pin "5") (pinfunction "R8_5") (pintype "passive"))
    )
    (net (code "65") (name "/1_ROW8") (class "Default")
      (node (ref "U13") (pin "9") (pinfunction "R1_9") (pintype "passive"))
      (node (ref "U15") (pin "4") (pinfunction "ROW8_4") (pintype "passive"))
      (node (ref "U17") (pin "9") (pinfunction "R1_9") (pintype "passive"))
    )
    (net (code "66") (name "/1_ROW9") (class "Default")
      (node (ref "U13") (pin "14") (pinfunction "R2_14") (pintype "passive"))
      (node (ref "U15") (pin "3") (pinfunction "ROW9_3") (pintype "passive"))
      (node (ref "U17") (pin "14") (pinfunction "R2_14") (pintype "passive"))
    )
    (net (code "67") (name "/1_ROW10") (class "Default")
      (node (ref "U13") (pin "8") (pinfunction "R3_8") (pintype "passive"))
      (node (ref "U15") (pin "2") (pinfunction "ROW10_2") (pintype "passive"))
      (node (ref "U17") (pin "8") (pinfunction "R3_8") (pintype "passive"))
    )
    (net (code "68") (name "/1_ROW11") (class "Default")
      (node (ref "U13") (pin "12") (pinfunction "R4_12") (pintype "passive"))
      (node (ref "U15") (pin "1") (pinfunction "ROW11_1") (pintype "passive"))
      (node (ref "U17") (pin "12") (pinfunction "R4_12") (pintype "passive"))
    )
    (net (code "69") (name "/1_ROW12") (class "Default")
      (node (ref "U13") (pin "1") (pinfunction "R5_1") (pintype "passive"))
      (node (ref "U15") (pin "52") (pinfunction "ROW12_52") (pintype "passive"))
      (node (ref "U17") (pin "1") (pinfunction "R5_1") (pintype "passive"))
    )
    (net (code "70") (name "/1_ROW13") (class "Default")
      (node (ref "U13") (pin "7") (pinfunction "R6_7") (pintype "passive"))
      (node (ref "U15") (pin "51") (pinfunction "ROW13_51") (pintype "passive"))
      (node (ref "U17") (pin "7") (pinfunction "R6_7") (pintype "passive"))
    )
    (net (code "71") (name "/1_ROW14") (class "Default")
      (node (ref "U13") (pin "2") (pinfunction "R7_2") (pintype "passive"))
      (node (ref "U15") (pin "50") (pinfunction "ROW14_50") (pintype "passive"))
      (node (ref "U17") (pin "2") (pinfunction "R7_2") (pintype "passive"))
    )
    (net (code "72") (name "/1_ROW15") (class "Default")
      (node (ref "U13") (pin "5") (pinfunction "R8_5") (pintype "passive"))
      (node (ref "U15") (pin "49") (pinfunction "ROW15_49") (pintype "passive"))
      (node (ref "U17") (pin "5") (pinfunction "R8_5") (pintype "passive"))
    )
    (net (code "73") (name "/1_ROW16") (class "Default")
      (node (ref "U14") (pin "9") (pinfunction "R1_9") (pintype "passive"))
      (node (ref "U15") (pin "48") (pinfunction "ROW16_48") (pintype "passive"))
      (node (ref "U18") (pin "9") (pinfunction "R1_9") (pintype "passive"))
    )
    (net (code "74") (name "/1_ROW17") (class "Default")
      (node (ref "U14") (pin "14") (pinfunction "R2_14") (pintype "passive"))
      (node (ref "U15") (pin "47") (pinfunction "ROW17_47") (pintype "passive"))
      (node (ref "U18") (pin "14") (pinfunction "R2_14") (pintype "passive"))
    )
    (net (code "75") (name "/1_ROW18") (class "Default")
      (node (ref "U14") (pin "8") (pinfunction "R3_8") (pintype "passive"))
      (node (ref "U15") (pin "46") (pinfunction "ROW18_46") (pintype "passive"))
      (node (ref "U18") (pin "8") (pinfunction "R3_8") (pintype "passive"))
    )
    (net (code "76") (name "/1_ROW19") (class "Default")
      (node (ref "U14") (pin "12") (pinfunction "R4_12") (pintype "passive"))
      (node (ref "U15") (pin "45") (pinfunction "ROW19_45") (pintype "passive"))
      (node (ref "U18") (pin "12") (pinfunction "R4_12") (pintype "passive"))
    )
    (net (code "77") (name "/1_ROW20") (class "Default")
      (node (ref "U14") (pin "1") (pinfunction "R5_1") (pintype "passive"))
      (node (ref "U15") (pin "44") (pinfunction "ROW20_44") (pintype "passive"))
      (node (ref "U18") (pin "1") (pinfunction "R5_1") (pintype "passive"))
    )
    (net (code "78") (name "/1_ROW21") (class "Default")
      (node (ref "U14") (pin "7") (pinfunction "R6_7") (pintype "passive"))
      (node (ref "U15") (pin "43") (pinfunction "ROW21_43") (pintype "passive"))
      (node (ref "U18") (pin "7") (pinfunction "R6_7") (pintype "passive"))
    )
    (net (code "79") (name "/1_ROW22") (class "Default")
      (node (ref "U14") (pin "2") (pinfunction "R7_2") (pintype "passive"))
      (node (ref "U15") (pin "42") (pinfunction "ROW22_42") (pintype "passive"))
      (node (ref "U18") (pin "2") (pinfunction "R7_2") (pintype "passive"))
    )
    (net (code "80") (name "/1_ROW23") (class "Default")
      (node (ref "U14") (pin "5") (pinfunction "R8_5") (pintype "passive"))
      (node (ref "U15") (pin "41") (pinfunction "ROW23_41") (pintype "passive"))
      (node (ref "U18") (pin "5") (pinfunction "R8_5") (pintype "passive"))
    )
    (net (code "81") (name "/ANT") (class "Default")
      (node (ref "U1") (pin "2") (pinfunction "ANT_2") (pintype "passive"))
    )
    (net (code "82") (name "/BUTTON") (class "Default")
      (node (ref "J1") (pin "2") (pinfunction "2_2") (pintype "passive"))
      (node (ref "U3") (pin "32") (pinfunction "PA11_32") (pintype "passive"))
    )
    (net (code "83") (name "/CS_0_HT1632") (class "Default")
      (node (ref "U3") (pin "28") (pinfunction "PB15_28") (pintype "passive"))
      (node (ref "U8") (pin "19") (pinfunction "~{CS}_19") (pintype "passive"))
    )
    (net (code "84") (name "/CS_1_HT1632") (class "Default")
      (node (ref "U15") (pin "19") (pinfunction "~{CS}_19") (pintype "passive"))
      (node (ref "U3") (pin "22") (pinfunction "PB11_22") (pintype "passive"))
    )
    (net (code "85") (name "/CS_GT20L16") (class "Default")
      (node (ref "U2") (pin "3") (pinfunction "CS#_3") (pintype "passive"))
      (node (ref "U3") (pin "46") (pinfunction "PB9_46") (pintype "passive"))
    )
    (net (code "86") (name "/DATA_HT1632") (class "Default")
      (node (ref "U15") (pin "16") (pinfunction "DATA_16") (pintype "passive"))
      (node (ref "U3") (pin "25") (pinfunction "PB12_25") (pintype "passive"))
      (node (ref "U8") (pin "16") (pinfunction "DATA_16") (pintype "passive"))
    )
    (net (code "87") (name "/OSCIN") (class "Default")
      (node (ref "C2") (pin "2") (pinfunction "2_2") (pintype "passive"))
      (node (ref "U3") (pin "5") (pinfunction "XTAL-IN_5") (pintype "passive"))
      (node (ref "XT1") (pin "3") (pinfunction "2_3") (pintype "passive"))
    )
    (net (code "88") (name "/OSCOUT") (class "Default")
      (node (ref "C1") (pin "2") (pinfunction "2_2") (pintype "passive"))
      (node (ref "U3") (pin "6") (pinfunction "XTAL-OUT_6") (pintype "passive"))
      (node (ref "XT1") (pin "1") (pinfunction "1_1") (pintype "passive"))
    )
    (net (code "89") (name "/RD_HT1632") (class "Default")
      (node (ref "U15") (pin "18") (pinfunction "~{RD}_18") (pintype "passive"))
      (node (ref "U3") (pin "27") (pinfunction "PB14_27") (pintype "passive"))
      (node (ref "U8") (pin "18") (pinfunction "~{RD}_18") (pintype "passive"))
    )
    (net (code "90") (name "/RESET_STM32") (class "Default")
      (node (ref "C3") (pin "1") (pinfunction "1_1") (pintype "passive"))
      (node (ref "R1") (pin "1") (pinfunction "1_1") (pintype "passive"))
      (node (ref "U3") (pin "7") (pinfunction "NRST_7") (pintype "passive"))
    )
    (net (code "91") (name "/SCL_GT20L16") (class "Default")
      (node (ref "U2") (pin "1") (pinfunction "SCLK_1") (pintype "passive"))
      (node (ref "U3") (pin "45") (pinfunction "PB8_45") (pintype "passive"))
    )
    (net (code "92") (name "/SI_GT20L16") (class "Default")
      (node (ref "U2") (pin "6") (pinfunction "SI_6") (pintype "passive"))
      (node (ref "U3") (pin "43") (pinfunction "PB7_43") (pintype "passive"))
    )
    (net (code "93") (name "/SO_GT20L16") (class "Default")
      (node (ref "U2") (pin "5") (pinfunction "SO_5") (pintype "passive"))
      (node (ref "U3") (pin "42") (pinfunction "PB6_42") (pintype "passive"))
    )
    (net (code "94") (name "/STM32_RX") (class "Default")
      (node (ref "U1") (pin "15") (pinfunction "UART_TX_15") (pintype "passive"))
      (node (ref "U3") (pin "31") (pinfunction "PA10_31") (pintype "passive"))
    )
    (net (code "95") (name "/STM32_TX") (class "Default")
      (node (ref "U1") (pin "14") (pinfunction "UART_RX_14") (pintype "passive"))
      (node (ref "U3") (pin "30") (pinfunction "PA9_30") (pintype "passive"))
    )
    (net (code "96") (name "/SWCLK") (class "Default")
      (node (ref "P1") (pin "4") (pinfunction "4_4") (pintype "passive"))
      (node (ref "U3") (pin "37") (pinfunction "SWCLK_37") (pintype "passive"))
    )
    (net (code "97") (name "/SWDIO") (class "Default")
      (node (ref "P1") (pin "3") (pinfunction "3_3") (pintype "passive"))
      (node (ref "U3") (pin "34") (pinfunction "SWDIO_34") (pintype "passive"))
    )
    (net (code "98") (name "/WR_HT1632") (class "Default")
      (node (ref "U15") (pin "17") (pinfunction "~{WR}_17") (pintype "passive"))
      (node (ref "U3") (pin "26") (pinfunction "PB13_26") (pintype "passive"))
      (node (ref "U8") (pin "17") (pinfunction "~{WR}_17") (pintype "passive"))
    )
    (net (code "99") (name "GND") (class "Default")
      (node (ref "C1") (pin "1") (pinfunction "1_1") (pintype "passive"))
      (node (ref "C10") (pin "1") (pinfunction "1_1") (pintype "passive"))
      (node (ref "C11") (pin "1") (pinfunction "1_1") (pintype "passive"))
      (node (ref "C12") (pin "2") (pinfunction "2_2") (pintype "passive"))
      (node (ref "C13") (pin "2") (pinfunction "2_2") (pintype "passive"))
      (node (ref "C14") (pin "2") (pinfunction "2_2") (pintype "passive"))
      (node (ref "C15") (pin "1") (pinfunction "1_1") (pintype "passive"))
      (node (ref "C16") (pin "1") (pinfunction "1_1") (pintype "passive"))
      (node (ref "C17") (pin "1") (pinfunction "1_1") (pintype "passive"))
      (node (ref "C18") (pin "1") (pinfunction "1_1") (pintype "passive"))
      (node (ref "C19") (pin "1") (pinfunction "1_1") (pintype "passive"))
      (node (ref "C2") (pin "1") (pinfunction "1_1") (pintype "passive"))
      (node (ref "C20") (pin "1") (pinfunction "1_1") (pintype "passive"))
      (node (ref "C3") (pin "2") (pinfunction "2_2") (pintype "passive"))
      (node (ref "C4") (pin "2") (pinfunction "2_2") (pintype "passive"))
      (node (ref "C5") (pin "1") (pinfunction "1_1") (pintype "passive"))
      (node (ref "C6") (pin "1") (pinfunction "1_1") (pintype "passive"))
      (node (ref "C7") (pin "1") (pinfunction "1_1") (pintype "passive"))
      (node (ref "C8") (pin "2") (pinfunction "2_2") (pintype "passive"))
      (node (ref "C9") (pin "1") (pinfunction "1_1") (pintype "passive"))
      (node (ref "J1") (pin "1") (pinfunction "1_1") (pintype "passive"))
      (node (ref "J2") (pin "1") (pinfunction "1_1") (pintype "passive"))
      (node (ref "P1") (pin "2") (pinfunction "2_2") (pintype "passive"))
      (node (ref "R2") (pin "1") (pinfunction "1_1") (pintype "passive"))
      (node (ref "R3") (pin "1") (pinfunction "1_1") (pintype "passive"))
      (node (ref "R4") (pin "2") (pinfunction "2_2") (pintype "passive"))
      (node (ref "U1") (pin "1") (pinfunction "GND_1") (pintype "passive"))
      (node (ref "U1") (pin "3") (pinfunction "GND_3") (pintype "passive"))
      (node (ref "U15") (pin "14") (pinfunction "VSS_14") (pintype "passive"))
      (node (ref "U15") (pin "25") (pinfunction "LED_VSS_25") (pintype "passive"))
      (node (ref "U15") (pin "36") (pinfunction "LED_VSS_36") (pintype "passive"))
      (node (ref "U2") (pin "2") (pinfunction "GND_2") (pintype "passive"))
      (node (ref "U3") (pin "23") (pinfunction "VSS_1_23") (pintype "passive"))
      (node (ref "U3") (pin "35") (pinfunction "VSS_2_35") (pintype "passive"))
      (node (ref "U3") (pin "47") (pinfunction "VSS_3_47") (pintype "passive"))
      (node (ref "U3") (pin "8") (pinfunction "VSSA_8") (pintype "passive"))
      (node (ref "U4") (pin "3") (pinfunction "DC-_3") (pintype "passive"))
      (node (ref "U8") (pin "14") (pinfunction "VSS_14") (pintype "passive"))
      (node (ref "U8") (pin "25") (pinfunction "LED_VSS_25") (pintype "passive"))
      (node (ref "U8") (pin "36") (pinfunction "LED_VSS_36") (pintype "passive"))
      (node (ref "XT1") (pin "2") (pinfunction "2_2") (pintype "passive"))
      (node (ref "XT1") (pin "4") (pinfunction "4_4") (pintype "passive"))
    )
    (net (code "100") (name "Net-(D1-A)") (class "Default")
      (node (ref "D1") (pin "1") (pinfunction "A_1") (pintype "passive"))
      (node (ref "U1") (pin "13") (pinfunction "LED_13") (pintype "passive"))
    )
    (net (code "101") (name "Net-(D1-K)") (class "Default")
      (node (ref "D1") (pin "2") (pinfunction "K_2") (pintype "passive"))
      (node (ref "R2") (pin "2") (pinfunction "2_2") (pintype "passive"))
    )
    (net (code "102") (name "Net-(P2-Pad1)") (class "Default")
      (node (ref "P2") (pin "1") (pinfunction "1_1") (pintype "passive"))
      (node (ref "P3") (pin "3") (pinfunction "3_3") (pintype "passive"))
    )
    (net (code "103") (name "Net-(P2-Pad2)") (class "Default")
      (node (ref "P2") (pin "2") (pinfunction "2_2") (pintype "passive"))
      (node (ref "P3") (pin "1") (pinfunction "1_1") (pintype "passive"))
    )
    (net (code "104") (name "Net-(P3-Pad2)") (class "Default")
      (node (ref "P3") (pin "2") (pinfunction "2_2") (pintype "passive"))
      (node (ref "U4") (pin "2") (pinfunction "AC_2") (pintype "passive"))
    )
    (net (code "105") (name "Net-(P3-Pad4)") (class "Default")
      (node (ref "P3") (pin "4") (pinfunction "4_4") (pintype "passive"))
      (node (ref "U4") (pin "1") (pinfunction "AC_1") (pintype "passive"))
    )
    (net (code "106") (name "Net-(U1-GPIO_KEY)") (class "Default")
      (node (ref "J2") (pin "2") (pinfunction "2_2") (pintype "passive"))
      (node (ref "U1") (pin "12") (pinfunction "GPIO_KEY_12") (pintype "passive"))
    )
    (net (code "107") (name "Net-(U3-BOOT0)") (class "Default")
      (node (ref "R3") (pin "2") (pinfunction "2_2") (pintype "passive"))
      (node (ref "U3") (pin "44") (pinfunction "BOOT0_44") (pintype "passive"))
    )
    (net (code "108") (name "Net-(U3-PB2)") (class "Default")
      (node (ref "R4") (pin "1") (pinfunction "1_1") (pintype "passive"))
      (node (ref "U3") (pin "20") (pinfunction "PB2_20") (pintype "passive"))
    )
    (net (code "109") (name "VCC_3.3") (class "Default")
      (node (ref "C10") (pin "2") (pinfunction "2_2") (pintype "passive"))
      (node (ref "C11") (pin "2") (pinfunction "2_2") (pintype "passive"))
      (node (ref "C12") (pin "1") (pinfunction "1_1") (pintype "passive"))
      (node (ref "C13") (pin "1") (pinfunction "1_1") (pintype "passive"))
      (node (ref "C14") (pin "1") (pinfunction "1_1") (pintype "passive"))
      (node (ref "C15") (pin "2") (pinfunction "2_2") (pintype "passive"))
      (node (ref "C16") (pin "2") (pinfunction "2_2") (pintype "passive"))
      (node (ref "C17") (pin "2") (pinfunction "2_2") (pintype "passive"))
      (node (ref "C18") (pin "2") (pinfunction "2_2") (pintype "passive"))
      (node (ref "C19") (pin "2") (pinfunction "2_2") (pintype "passive"))
      (node (ref "C20") (pin "2") (pinfunction "2_2") (pintype "passive"))
      (node (ref "C4") (pin "1") (pinfunction "1_1") (pintype "passive"))
      (node (ref "C5") (pin "2") (pinfunction "2_2") (pintype "passive"))
      (node (ref "C6") (pin "2") (pinfunction "2_2") (pintype "passive"))
      (node (ref "C7") (pin "2") (pinfunction "2_2") (pintype "passive"))
      (node (ref "C8") (pin "1") (pinfunction "1_1") (pintype "passive"))
      (node (ref "C9") (pin "2") (pinfunction "2_2") (pintype "passive"))
      (node (ref "P1") (pin "1") (pinfunction "1_1") (pintype "passive"))
      (node (ref "R1") (pin "2") (pinfunction "2_2") (pintype "passive"))
      (node (ref "U1") (pin "4") (pinfunction "VCC_4") (pintype "passive"))
      (node (ref "U15") (pin "21") (pinfunction "VDD_21") (pintype "passive"))
      (node (ref "U15") (pin "38") (pinfunction "LED_VDD_38") (pintype "passive"))
      (node (ref "U15") (pin "7") (pinfunction "LED_VDD_7") (pintype "passive"))
      (node (ref "U2") (pin "4") (pinfunction "VCC_4") (pintype "passive"))
      (node (ref "U3") (pin "1") (pinfunction "VBAT_1") (pintype "passive"))
      (node (ref "U3") (pin "24") (pinfunction "VDD_1_24") (pintype "passive"))
      (node (ref "U3") (pin "36") (pinfunction "VDD_2_36") (pintype "passive"))
      (node (ref "U3") (pin "48") (pinfunction "VDD_3_48") (pintype "passive"))
      (node (ref "U3") (pin "9") (pinfunction "VDDA_9") (pintype "passive"))
      (node (ref "U4") (pin "4") (pinfunction "DC+_4") (pintype "passive"))
      (node (ref "U8") (pin "21") (pinfunction "VDD_21") (pintype "passive"))
      (node (ref "U8") (pin "38") (pinfunction "LED_VDD_38") (pintype "passive"))
      (node (ref "U8") (pin "7") (pinfunction "LED_VDD_7") (pintype "passive"))
    )
    (net (code "110") (name "unconnected-(U1-NC-Pad5)") (class "Default")
      (node (ref "U1") (pin "5") (pinfunction "NC_5") (pintype "passive+no_connect"))
    )
    (net (code "111") (name "unconnected-(U1-NC-Pad6)") (class "Default")
      (node (ref "U1") (pin "6") (pinfunction "NC_6") (pintype "passive+no_connect"))
    )
    (net (code "112") (name "unconnected-(U1-NC-Pad7)") (class "Default")
      (node (ref "U1") (pin "7") (pinfunction "NC_7") (pintype "passive+no_connect"))
    )
    (net (code "113") (name "unconnected-(U1-NC-Pad8)") (class "Default")
      (node (ref "U1") (pin "8") (pinfunction "NC_8") (pintype "passive+no_connect"))
    )
    (net (code "114") (name "unconnected-(U1-NC-Pad9)") (class "Default")
      (node (ref "U1") (pin "9") (pinfunction "NC_9") (pintype "passive+no_connect"))
    )
    (net (code "115") (name "unconnected-(U1-NC-Pad10)") (class "Default")
      (node (ref "U1") (pin "10") (pinfunction "NC_10") (pintype "passive+no_connect"))
    )
    (net (code "116") (name "unconnected-(U1-NC-Pad11)") (class "Default")
      (node (ref "U1") (pin "11") (pinfunction "NC_11") (pintype "passive+no_connect"))
    )
    (net (code "117") (name "unconnected-(U1-RST-Pad16)") (class "Default")
      (node (ref "U1") (pin "16") (pinfunction "RST_16") (pintype "passive+no_connect"))
    )
    (net (code "118") (name "unconnected-(U3-PA0-Pad10)") (class "Default")
      (node (ref "U3") (pin "10") (pinfunction "PA0_10") (pintype "passive+no_connect"))
    )
    (net (code "119") (name "unconnected-(U3-PA1-Pad11)") (class "Default")
      (node (ref "U3") (pin "11") (pinfunction "PA1_11") (pintype "passive+no_connect"))
    )
    (net (code "120") (name "unconnected-(U3-PA2-Pad12)") (class "Default")
      (node (ref "U3") (pin "12") (pinfunction "PA2_12") (pintype "passive+no_connect"))
    )
    (net (code "121") (name "unconnected-(U3-PA3-Pad13)") (class "Default")
      (node (ref "U3") (pin "13") (pinfunction "PA3_13") (pintype "passive+no_connect"))
    )
    (net (code "122") (name "unconnected-(U3-PA4-Pad14)") (class "Default")
      (node (ref "U3") (pin "14") (pinfunction "PA4_14") (pintype "passive+no_connect"))
    )
    (net (code "123") (name "unconnected-(U3-PA5-Pad15)") (class "Default")
      (node (ref "U3") (pin "15") (pinfunction "PA5_15") (pintype "passive+no_connect"))
    )
    (net (code "124") (name "unconnected-(U3-PA6-Pad16)") (class "Default")
      (node (ref "U3") (pin "16") (pinfunction "PA6_16") (pintype "passive+no_connect"))
    )
    (net (code "125") (name "unconnected-(U3-PA7-Pad17)") (class "Default")
      (node (ref "U3") (pin "17") (pinfunction "PA7_17") (pintype "passive+no_connect"))
    )
    (net (code "126") (name "unconnected-(U3-PA8-Pad29)") (class "Default")
      (node (ref "U3") (pin "29") (pinfunction "PA8_29") (pintype "passive+no_connect"))
    )
    (net (code "127") (name "unconnected-(U3-PA12-Pad33)") (class "Default")
      (node (ref "U3") (pin "33") (pinfunction "PA12_33") (pintype "passive+no_connect"))
    )
    (net (code "128") (name "unconnected-(U3-PA15-Pad38)") (class "Default")
      (node (ref "U3") (pin "38") (pinfunction "PA15_38") (pintype "passive+no_connect"))
    )
    (net (code "129") (name "unconnected-(U3-PB0-Pad18)") (class "Default")
      (node (ref "U3") (pin "18") (pinfunction "PB0_18") (pintype "passive+no_connect"))
    )
    (net (code "130") (name "unconnected-(U3-PB1-Pad19)") (class "Default")
      (node (ref "U3") (pin "19") (pinfunction "PB1_19") (pintype "passive+no_connect"))
    )
    (net (code "131") (name "unconnected-(U3-PB3-Pad39)") (class "Default")
      (node (ref "U3") (pin "39") (pinfunction "PB3_39") (pintype "passive+no_connect"))
    )
    (net (code "132") (name "unconnected-(U3-PB4-Pad40)") (class "Default")
      (node (ref "U3") (pin "40") (pinfunction "PB4_40") (pintype "passive+no_connect"))
    )
    (net (code "133") (name "unconnected-(U3-PB5-Pad41)") (class "Default")
      (node (ref "U3") (pin "41") (pinfunction "PB5_41") (pintype "passive+no_connect"))
    )
    (net (code "134") (name "unconnected-(U3-PB10-Pad21)") (class "Default")
      (node (ref "U3") (pin "21") (pinfunction "PB10_21") (pintype "passive"))
    )
    (net (code "135") (name "unconnected-(U3-PC13-Pad2)") (class "Default")
      (node (ref "U3") (pin "2") (pinfunction "PC13_2") (pintype "passive+no_connect"))
    )
    (net (code "136") (name "unconnected-(U3-PC14-Pad3)") (class "Default")
      (node (ref "U3") (pin "3") (pinfunction "PC14_3") (pintype "passive+no_connect"))
    )
    (net (code "137") (name "unconnected-(U3-PC15-Pad4)") (class "Default")
      (node (ref "U3") (pin "4") (pinfunction "PC15_4") (pintype "passive+no_connect"))
    )
    (net (code "138") (name "unconnected-(U8-OSC-Pad15)") (class "Default")
      (node (ref "U8") (pin "15") (pinfunction "OSC_15") (pintype "passive+no_connect"))
    )
    (net (code "139") (name "unconnected-(U8-SYNC-Pad20)") (class "Default")
      (node (ref "U8") (pin "20") (pinfunction "SYNC_20") (pintype "passive+no_connect"))
    )
    (net (code "140") (name "unconnected-(U15-OSC-Pad15)") (class "Default")
      (node (ref "U15") (pin "15") (pinfunction "OSC_15") (pintype "passive+no_connect"))
    )
    (net (code "141") (name "unconnected-(U15-SYNC-Pad20)") (class "Default")
      (node (ref "U15") (pin "20") (pinfunction "SYNC_20") (pintype "passive+no_connect"))
    )
  )
)
